# LTE_GPS.net
KiCad netlist of a schematic drawn in Altium Designer
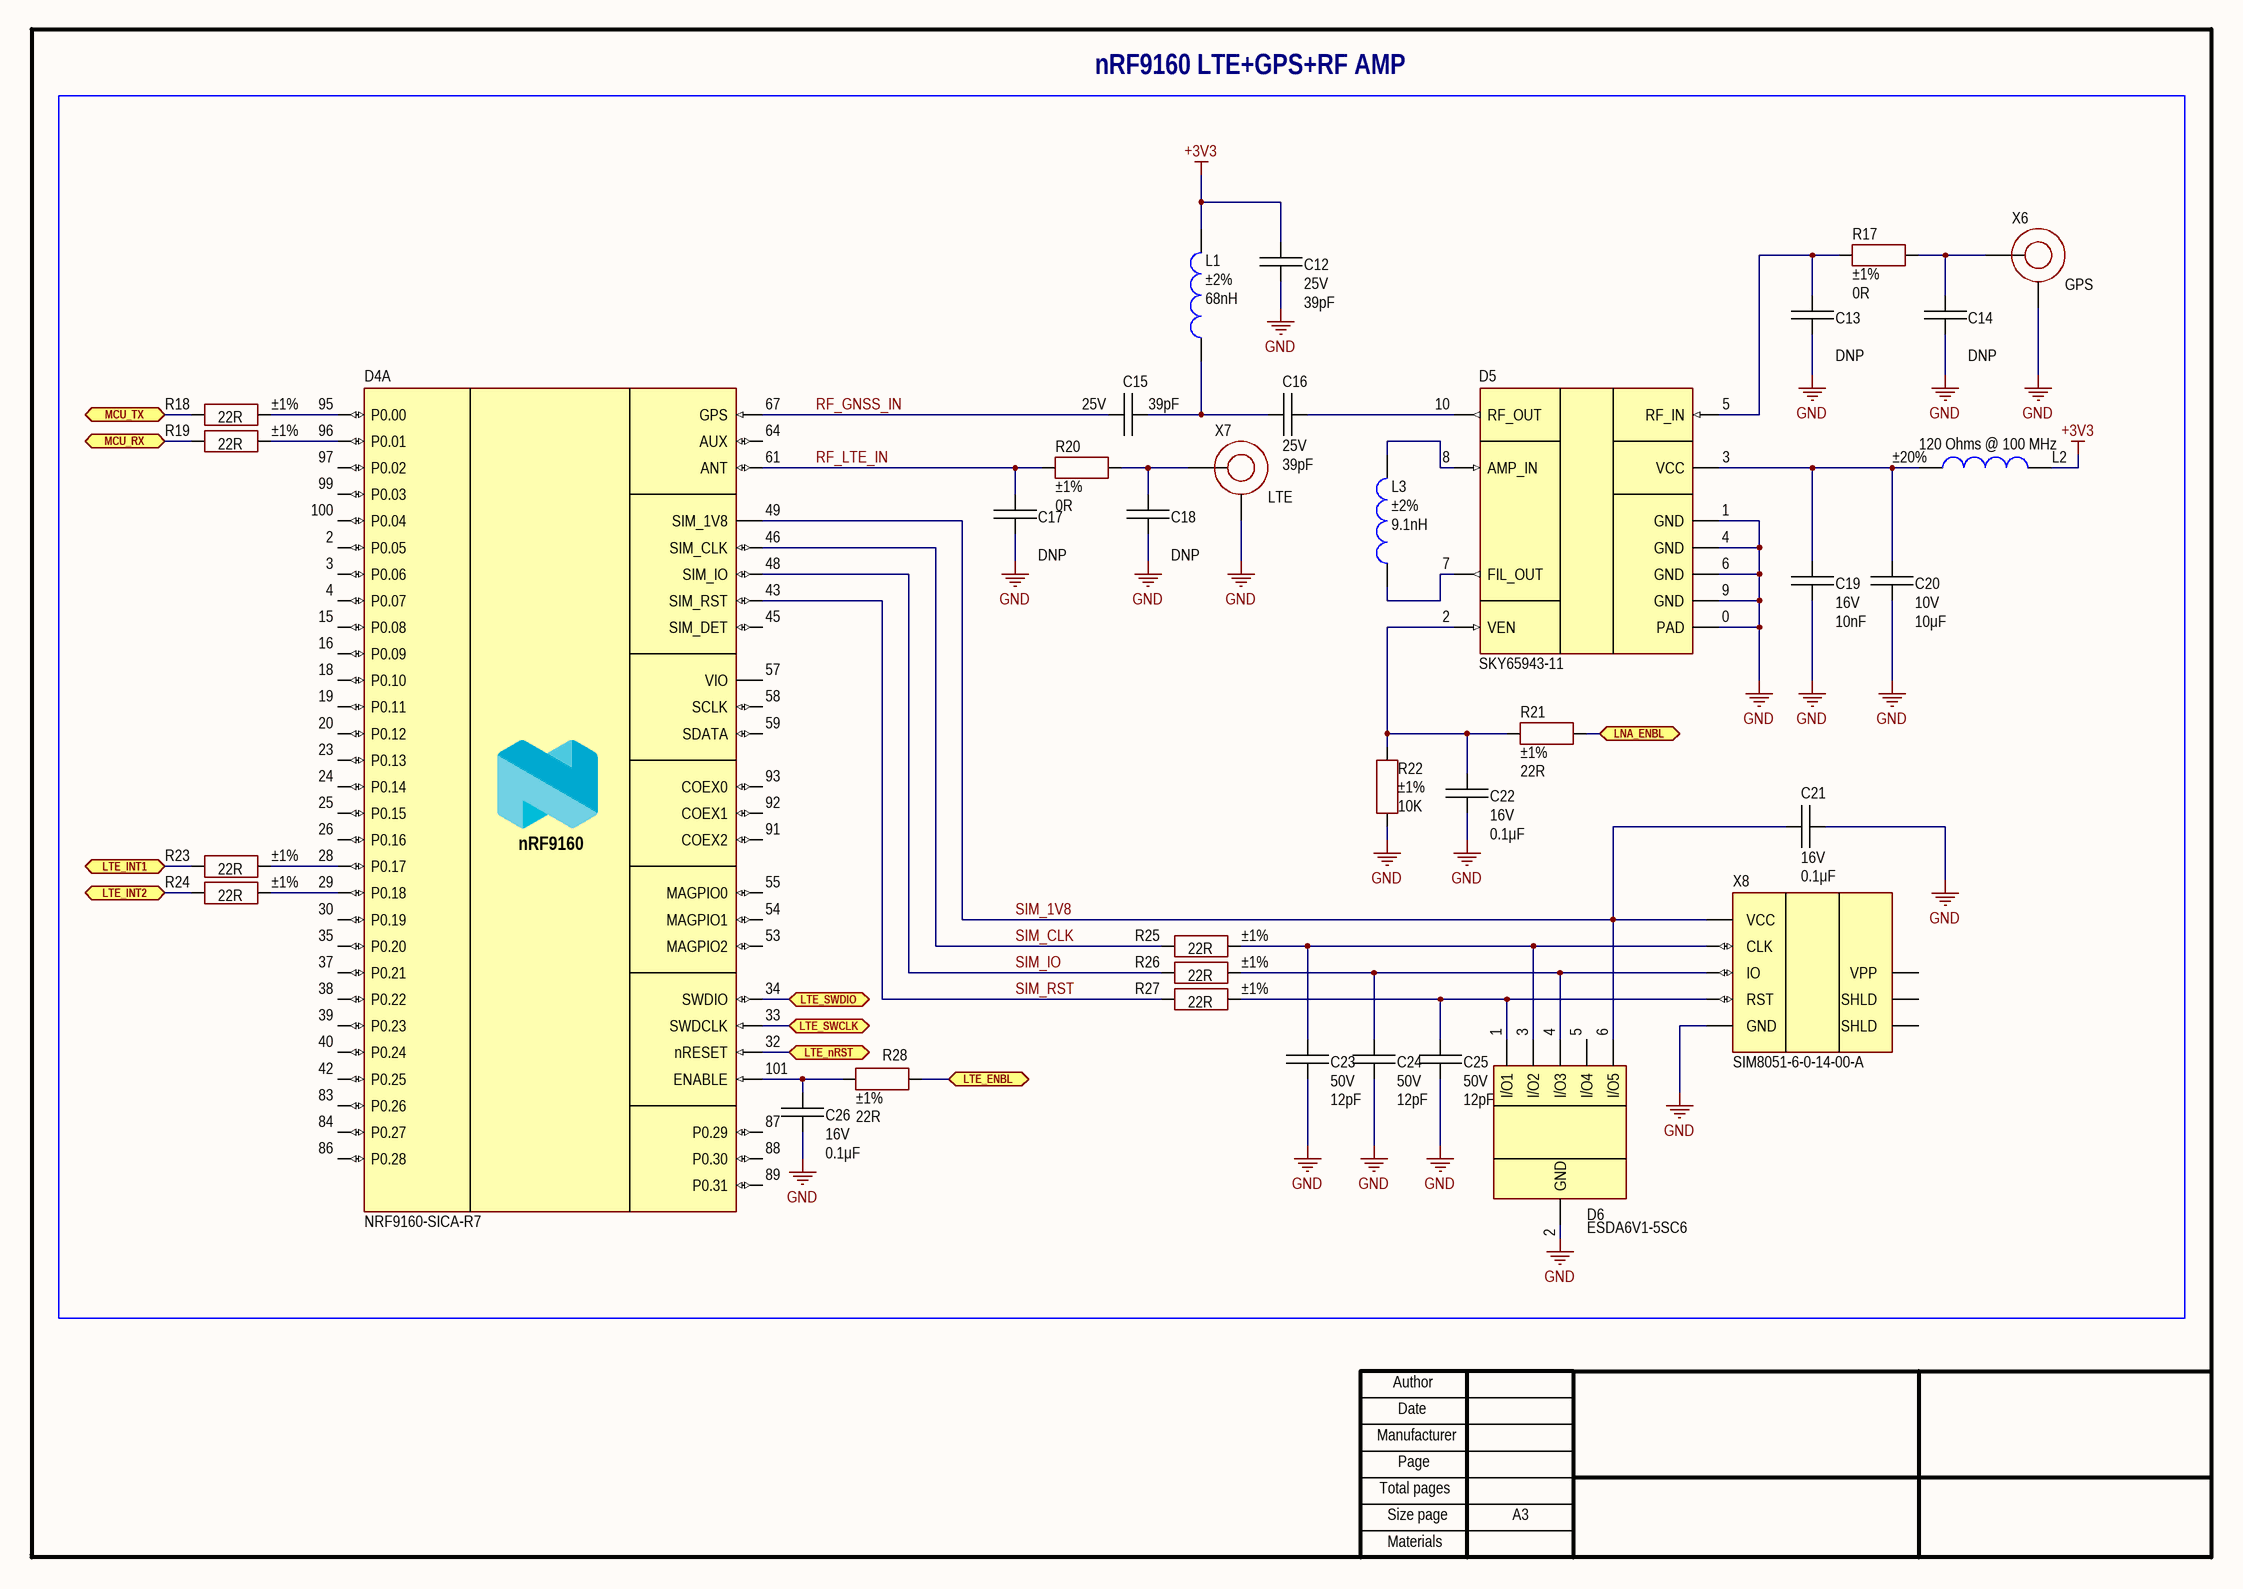
[diagram p0: LTE+GPS.SchDoc]

(export (version "E")
  (design (tool "Eeschema 10.0.6"))
  (components
    (comp (ref "C12")
      (value "39pF")
      (footprint "CAP: 0201")
      (description "39 pF ±5% 25V Ceramic Capacitor C0G, NP0 0201 (0603 Metric)")
      (fields
        (field (name "MANUFACTURER") "Murata Electronics")
        (field (name "PARTNUMBER") "GRM0335C1E390JA01D")
        (field (name "VOLTAGE") "25V")
      )
      (libsource (lib "capacitor") (part "Ceramic_0201"))
    )
    (comp (ref "C13")
      (value "DNP")
      (footprint "CAP: 0201")
      (fields (field (name "VALUEMANUFACTURERPARTNUMBER") "Ceramic capacitor, DNP, , , , 0201, -55...+125°C"))
      (libsource (lib "capacitor") (part "Ceramic_0201"))
    )
    (comp (ref "C14")
      (value "DNP")
      (footprint "CAP: 0201")
      (fields (field (name "VALUEMANUFACTURERPARTNUMBER") "Ceramic capacitor, DNP, , , , 0201, -55...+125°C"))
      (libsource (lib "capacitor") (part "Ceramic_0201"))
    )
    (comp (ref "C15")
      (value "39pF")
      (footprint "CAP: 0201")
      (description "39 pF ±5% 25V Ceramic Capacitor C0G, NP0 0201 (0603 Metric)")
      (fields
        (field (name "MANUFACTURER") "Murata Electronics")
        (field (name "PARTNUMBER") "GRM0335C1E390JA01D")
        (field (name "VOLTAGE") "25V")
      )
      (libsource (lib "capacitor") (part "Ceramic_0201"))
    )
    (comp (ref "C16")
      (value "39pF")
      (footprint "CAP: 0201")
      (description "39 pF ±5% 25V Ceramic Capacitor C0G, NP0 0201 (0603 Metric)")
      (fields
        (field (name "MANUFACTURER") "Murata Electronics")
        (field (name "PARTNUMBER") "GRM0335C1E390JA01D")
        (field (name "VOLTAGE") "25V")
      )
      (libsource (lib "capacitor") (part "Ceramic_0201"))
    )
    (comp (ref "C17")
      (value "DNP")
      (footprint "CAP: 0201")
      (fields (field (name "VALUEMANUFACTURERPARTNUMBER") "Ceramic capacitor, DNP, , , , 0201, -55...+125°C"))
      (libsource (lib "capacitor") (part "Ceramic_0201"))
    )
    (comp (ref "C18")
      (value "DNP")
      (footprint "CAP: 0201")
      (fields (field (name "VALUEMANUFACTURERPARTNUMBER") "Ceramic capacitor, DNP, , , , 0201, -55...+125°C"))
      (libsource (lib "capacitor") (part "Ceramic_0201"))
    )
    (comp (ref "C19")
      (value "10nF")
      (footprint "CAP: 0402_NO_SILK")
      (description "0.1 µF ±10% 16V Ceramic Capacitor X7R 0402 (1005 Metric)")
      (fields
        (field (name "MANUFACTURER") "Yageo")
        (field (name "PARTNUMBER") "CC0805JKNPO7BN103")
        (field (name "VOLTAGE") "16V")
      )
      (libsource (lib "capacitor") (part "Ceramic_0402"))
    )
    (comp (ref "C20")
      (value "10μF")
      (footprint "CAP: 0805")
      (description "10 µF ±10% 10V Ceramic Capacitor X7R 0805 (2012 Metric)")
      (fields
        (field (name "MANUFACTURER") "Yageo")
        (field (name "PARTNUMBER") "CC0805KFX7R6BB106")
        (field (name "VOLTAGE") "10V")
      )
      (libsource (lib "capacitor") (part "Ceramic_0805"))
    )
    (comp (ref "C21")
      (value "0.1μF")
      (footprint "CAP: 0402_NO_SILK")
      (description "0.1 µF ±10% 16V Ceramic Capacitor X7R 0402 (1005 Metric)")
      (fields
        (field (name "MANUFACTURER") "Yageo")
        (field (name "PARTNUMBER") "CC0402KRX7R7BB104")
        (field (name "VOLTAGE") "16V")
      )
      (libsource (lib "capacitor") (part "Ceramic_0402"))
    )
    (comp (ref "C22")
      (value "0.1μF")
      (footprint "CAP: 0805")
      (fields
        (field (name "MANUFACTURER") "Yageo")
        (field (name "PARTNUMBER") "CC0805KRX7R7BB104")
        (field (name "VALUEMANUFACTURERPARTNUMBER") "Ceramic capacitor, 0.1μF, X7R, ±10%, 16V, 0805, -55...+125°C")
        (field (name "VOLTAGE") "16V")
      )
      (libsource (lib "capacitor") (part "Ceramic_0805"))
    )
    (comp (ref "C23")
      (value "12pF")
      (footprint "CAP: 0805")
      (description "12 pF ±1% 50V Ceramic Capacitor C0G, NP0 0805 (2012 Metric)")
      (fields
        (field (name "MANUFACTURER") "Yageo")
        (field (name "PARTNUMBER") "CC0805FRNPO9BN120")
        (field (name "VOLTAGE") "50V")
      )
      (libsource (lib "capacitor") (part "Ceramic_0805"))
    )
    (comp (ref "C24")
      (value "12pF")
      (footprint "CAP: 0805")
      (description "12 pF ±1% 50V Ceramic Capacitor C0G, NP0 0805 (2012 Metric)")
      (fields
        (field (name "MANUFACTURER") "Yageo")
        (field (name "PARTNUMBER") "CC0805FRNPO9BN120")
        (field (name "VOLTAGE") "50V")
      )
      (libsource (lib "capacitor") (part "Ceramic_0805"))
    )
    (comp (ref "C25")
      (value "12pF")
      (footprint "CAP: 0805")
      (description "12 pF ±1% 50V Ceramic Capacitor C0G, NP0 0805 (2012 Metric)")
      (fields
        (field (name "MANUFACTURER") "Yageo")
        (field (name "PARTNUMBER") "CC0805FRNPO9BN120")
        (field (name "VOLTAGE") "50V")
      )
      (libsource (lib "capacitor") (part "Ceramic_0805"))
    )
    (comp (ref "C26")
      (value "0.1μF")
      (footprint "CAP: 0805")
      (fields
        (field (name "MANUFACTURER") "Yageo")
        (field (name "PARTNUMBER") "CC0805KRX7R7BB104")
        (field (name "VALUEMANUFACTURERPARTNUMBER") "Ceramic capacitor, 0.1μF, X7R, ±10%, 16V, 0805, -55...+125°C")
        (field (name "VOLTAGE") "16V")
      )
      (libsource (lib "capacitor") (part "Ceramic_0805"))
    )
    (comp (ref "D4")
      (value "~")
      (footprint "MOD: NRF9160")
      (description "LTE/GSM module")
      (fields
        (field (name "MANUFACTURER") "Nordic Semiconductor")
        (field (name "VALUEMANUFACTURERPARTNUMBER") "LTE/GSM module, LTE-M/NB-IoT/GPS, 2.4GHz, , , , , 3...5.5V, -40...+85°C, 127-LGA")
        (field (name "PARTNUMBER") "NRF9160-SICA-R7")
      )
      (libsource (lib "MyLib") (part "nRF9160"))
    )
    (comp (ref "D5")
      (value "~")
      (footprint "IC: SKY65943-11")
      (description "RF front-end")
      (fields
        (field (name "MANUFACTURER") "Skyworks Solutions")
        (field (name "VALUEMANUFACTURERPARTNUMBER") "IC RF amplifier, 2.7 GHz, 19dB, -40...+125°C, 10-SMD Module")
        (field (name "PARTNUMBER") "SKY65943-11")
      )
      (libsource (lib "MyLib") (part "SKY65943-11"))
    )
    (comp (ref "D6")
      (value "~")
      (footprint "SOT23-6")
      (description "TVS Array")
      (fields
        (field (name "MANUFACTURER") "STMicroelectronics")
        (field (name "VALUEMANUFACTURERPARTNUMBER") "TVS array, , 5A peak, 6.1V, , SOT-23-6, -40...+125°C")
        (field (name "PARTNUMBER") "ESDA6V1-5SC6")
      )
      (libsource (lib "MyLib") (part "ESDA6V1-5SC6"))
    )
    (comp (ref "L1")
      (value "68nH")
      (footprint "IND: 0402")
      (description "68 nH Unshielded Wirewound Inductor 320 mA 1.1Ohm Max 0402 (1005 Metric)")
      (fields
        (field (name "MANUFACTURER") "Murata Electronics")
        (field (name "PARTNUMBER") "LQW15AN68NG80D")
        (field (name "TOLERANCE") "±2%")
      )
      (libsource (lib "inductor") (part "Inductor_0402"))
    )
    (comp (ref "L2")
      (value "120 Ohms @ 100 MHz")
      (footprint "IND: 0805")
      (description "120 Ohms @ 100 MHz 1 Power Line Ferrite Bead 0805 (2012 Metric) 3A 30mOhm")
      (fields
        (field (name "MANUFACTURER") "Murata Electronics")
        (field (name "PARTNUMBER") "BLM21PG121SH1D")
        (field (name "TOLERANCE") "±20%")
      )
      (libsource (lib "inductor") (part "Inductor_0805"))
    )
    (comp (ref "L3")
      (value "9.1nH")
      (footprint "IND: 0402")
      (description "9.1 nH Unshielded Wirewound Inductor 1.4 A 80mOhm Max 0402 (1005 Metric)")
      (fields
        (field (name "MANUFACTURER") "Murata Electronics")
        (field (name "PARTNUMBER") "LQW15AN9N1G8ZD")
        (field (name "TOLERANCE") "±2%")
      )
      (libsource (lib "inductor") (part "Inductor_0402"))
    )
    (comp (ref "R17")
      (value "0R")
      (footprint "RES: 0201")
      (description "0 Ohms Jumper 0.05W, 1/20W Chip Resistor 0201 (0603 Metric) Moisture Resistant Thick Film")
      (fields
        (field (name "MANUFACTURER") "Yageo")
        (field (name "PARTNUMBER") "RC0201FR-070RL")
        (field (name "TOLERANCE") "±1%")
      )
      (libsource (lib "resistor") (part "Resistor_0201"))
    )
    (comp (ref "R18")
      (value "22R")
      (footprint "RES: 0805")
      (description "22 Ohms ±1% 0.125W, 1/8W Chip Resistor 0805 (2012 Metric) Moisture Resistant Thick Film")
      (fields
        (field (name "MANUFACTURER") "Yageo")
        (field (name "PARTNUMBER") "RC0805FR-0722RL")
        (field (name "TOLERANCE") "±1%")
      )
      (libsource (lib "resistor") (part "Resistor_0805"))
    )
    (comp (ref "R19")
      (value "22R")
      (footprint "RES: 0805")
      (description "22 Ohms ±1% 0.125W, 1/8W Chip Resistor 0805 (2012 Metric) Moisture Resistant Thick Film")
      (fields
        (field (name "MANUFACTURER") "Yageo")
        (field (name "PARTNUMBER") "RC0805FR-0722RL")
        (field (name "TOLERANCE") "±1%")
      )
      (libsource (lib "resistor") (part "Resistor_0805"))
    )
    (comp (ref "R20")
      (value "0R")
      (footprint "RES: 0201")
      (description "0 Ohms Jumper 0.05W, 1/20W Chip Resistor 0201 (0603 Metric) Moisture Resistant Thick Film")
      (fields
        (field (name "MANUFACTURER") "Yageo")
        (field (name "PARTNUMBER") "RC0201FR-070RL")
        (field (name "TOLERANCE") "±1%")
      )
      (libsource (lib "resistor") (part "Resistor_0201"))
    )
    (comp (ref "R21")
      (value "22R")
      (footprint "RES: 0805")
      (description "22 Ohms ±1% 0.125W, 1/8W Chip Resistor 0805 (2012 Metric) Moisture Resistant Thick Film")
      (fields
        (field (name "MANUFACTURER") "Yageo")
        (field (name "PARTNUMBER") "RC0805FR-0722RL")
        (field (name "TOLERANCE") "±1%")
      )
      (libsource (lib "") (part "Resistor_0805_1"))
    )
    (comp (ref "R22")
      (value "10K")
      (footprint "RES: 0805")
      (description "10 kOhms ±1% 0.125W, 1/8W Chip Resistor 0805 (2012 Metric) Moisture Resistant Thick Film")
      (fields
        (field (name "MANUFACTURER") "Yageo")
        (field (name "PARTNUMBER") "RC0805FR-0710KL")
        (field (name "TOLERANCE") "±1%")
      )
      (libsource (lib "") (part "Resistor_0805_2"))
    )
    (comp (ref "R23")
      (value "22R")
      (footprint "RES: 0805")
      (description "22 Ohms ±1% 0.125W, 1/8W Chip Resistor 0805 (2012 Metric) Moisture Resistant Thick Film")
      (fields
        (field (name "MANUFACTURER") "Yageo")
        (field (name "PARTNUMBER") "RC0805FR-0722RL")
        (field (name "TOLERANCE") "±1%")
      )
      (libsource (lib "resistor") (part "Resistor_0805"))
    )
    (comp (ref "R24")
      (value "22R")
      (footprint "RES: 0805")
      (description "22 Ohms ±1% 0.125W, 1/8W Chip Resistor 0805 (2012 Metric) Moisture Resistant Thick Film")
      (fields
        (field (name "MANUFACTURER") "Yageo")
        (field (name "PARTNUMBER") "RC0805FR-0722RL")
        (field (name "TOLERANCE") "±1%")
      )
      (libsource (lib "resistor") (part "Resistor_0805"))
    )
    (comp (ref "R25")
      (value "22R")
      (footprint "RES: 0805")
      (description "22 Ohms ±1% 0.125W, 1/8W Chip Resistor 0805 (2012 Metric) Moisture Resistant Thick Film")
      (fields
        (field (name "MANUFACTURER") "Yageo")
        (field (name "PARTNUMBER") "RC0805FR-0722RL")
        (field (name "TOLERANCE") "±1%")
      )
      (libsource (lib "resistor") (part "Resistor_0805"))
    )
    (comp (ref "R26")
      (value "22R")
      (footprint "RES: 0805")
      (description "22 Ohms ±1% 0.125W, 1/8W Chip Resistor 0805 (2012 Metric) Moisture Resistant Thick Film")
      (fields
        (field (name "MANUFACTURER") "Yageo")
        (field (name "PARTNUMBER") "RC0805FR-0722RL")
        (field (name "TOLERANCE") "±1%")
      )
      (libsource (lib "resistor") (part "Resistor_0805"))
    )
    (comp (ref "R27")
      (value "22R")
      (footprint "RES: 0805")
      (description "22 Ohms ±1% 0.125W, 1/8W Chip Resistor 0805 (2012 Metric) Moisture Resistant Thick Film")
      (fields
        (field (name "MANUFACTURER") "Yageo")
        (field (name "PARTNUMBER") "RC0805FR-0722RL")
        (field (name "TOLERANCE") "±1%")
      )
      (libsource (lib "resistor") (part "Resistor_0805"))
    )
    (comp (ref "R28")
      (value "22R")
      (footprint "RES: 0805")
      (description "22 Ohms ±1% 0.125W, 1/8W Chip Resistor 0805 (2012 Metric) Moisture Resistant Thick Film")
      (fields
        (field (name "MANUFACTURER") "Yageo")
        (field (name "PARTNUMBER") "RC0805FR-0722RL")
        (field (name "TOLERANCE") "±1%")
      )
      (libsource (lib "") (part "Resistor_0805_1"))
    )
    (comp (ref "X6")
      (value "~")
      (footprint "CON: u.Fl")
      (description "U.FL (UMCC) Connector Receptacle, Male Pin 50Ohm Surface Mount Solder")
      (fields
        (field (name "MANUFACTURER") "Hirose Electric")
        (field (name "VALUEMANUFACTURERPARTNUMBER") "Connector u.FL, 50 Ohm, 6GHz")
        (field (name "COMMENTTEXT") "GPS")
      )
      (libsource (lib "connector") (part "Connector_uFL"))
    )
    (comp (ref "X7")
      (value "~")
      (footprint "CON: u.Fl")
      (description "U.FL (UMCC) Connector Receptacle, Male Pin 50Ohm Surface Mount Solder")
      (fields
        (field (name "MANUFACTURER") "Hirose Electric")
        (field (name "VALUEMANUFACTURERPARTNUMBER") "Connector u.FL, 50 Ohm, 6GHz")
        (field (name "COMMENTTEXT") "LTE")
      )
      (libsource (lib "connector") (part "Connector_uFL"))
    )
    (comp (ref "X8")
      (value "~")
      (footprint "CON: SIM8051-6-0-14-00")
      (description "Connector")
      (fields
        (field (name "MANUFACTURER") "GCT")
        (field (name "VALUEMANUFACTURERPARTNUMBER") "Nano SIM, , , , ")
        (field (name "COMMENTTEXT") "SIM8051-6-0-14-00-A")
      )
      (libsource (lib "MyLib") (part "SIM8051-6-0-14-00-A"))
    )
  )
  (nets
    (net (code "1") (name "+3V3") (class "Default")
      (node (ref "C12") (pin "1") (pinfunction "1_1") (pintype "passive"))
      (node (ref "L1") (pin "1") (pinfunction "1_1") (pintype "passive"))
      (node (ref "L2") (pin "1") (pinfunction "1_1") (pintype "passive"))
    )
    (net (code "2") (name "/LNA_ENBL") (class "Default")
      (node (ref "R21") (pin "1") (pinfunction "1_1") (pintype "passive"))
    )
    (net (code "3") (name "/LTE_ENBL") (class "Default")
      (node (ref "R28") (pin "1") (pinfunction "1_1") (pintype "passive"))
    )
    (net (code "4") (name "/LTE_INT1") (class "Default")
      (node (ref "R23") (pin "1") (pinfunction "1_1") (pintype "passive"))
    )
    (net (code "5") (name "/LTE_INT2") (class "Default")
      (node (ref "R24") (pin "1") (pinfunction "1_1") (pintype "passive"))
    )
    (net (code "6") (name "/LTE_SWCLK") (class "Default")
      (node (ref "D4") (pin "33") (pinfunction "SWDCLK_33") (pintype "input"))
    )
    (net (code "7") (name "/LTE_SWDIO") (class "Default")
      (node (ref "D4") (pin "34") (pinfunction "SWDIO_34") (pintype "bidirectional"))
    )
    (net (code "8") (name "/LTE_nRST") (class "Default")
      (node (ref "D4") (pin "32") (pinfunction "nRESET_32") (pintype "input"))
    )
    (net (code "9") (name "/MCU_RX") (class "Default")
      (node (ref "R19") (pin "1") (pinfunction "1_1") (pintype "passive"))
    )
    (net (code "10") (name "/MCU_TX") (class "Default")
      (node (ref "R18") (pin "1") (pinfunction "1_1") (pintype "passive"))
    )
    (net (code "11") (name "/RF_GNSS_IN") (class "Default")
      (node (ref "C15") (pin "2") (pinfunction "2_2") (pintype "passive"))
      (node (ref "D4") (pin "67") (pinfunction "GPS_67") (pintype "input"))
    )
    (net (code "12") (name "/RF_LTE_IN") (class "Default")
      (node (ref "C17") (pin "2") (pinfunction "2_2") (pintype "passive"))
      (node (ref "D4") (pin "61") (pinfunction "ANT_61") (pintype "bidirectional"))
      (node (ref "R20") (pin "2") (pinfunction "2_2") (pintype "passive"))
    )
    (net (code "13") (name "/SIM_1V8") (class "Default")
      (node (ref "C21") (pin "1") (pinfunction "1_1") (pintype "passive"))
      (node (ref "D4") (pin "49") (pinfunction "SIM_1V8_49") (pintype "power_in"))
      (node (ref "D6") (pin "6") (pinfunction "I/O5_6") (pintype "passive"))
      (node (ref "X8") (pin "C1") (pinfunction "VCC_C1") (pintype "power_in"))
    )
    (net (code "14") (name "/SIM_CLK") (class "Default")
      (node (ref "D4") (pin "46") (pinfunction "SIM_CLK_46") (pintype "bidirectional"))
      (node (ref "R25") (pin "1") (pinfunction "1_1") (pintype "passive"))
    )
    (net (code "15") (name "/SIM_IO") (class "Default")
      (node (ref "D4") (pin "48") (pinfunction "SIM_IO_48") (pintype "bidirectional"))
      (node (ref "R26") (pin "1") (pinfunction "1_1") (pintype "passive"))
    )
    (net (code "16") (name "/SIM_RST") (class "Default")
      (node (ref "D4") (pin "43") (pinfunction "SIM_RST_43") (pintype "bidirectional"))
      (node (ref "R27") (pin "1") (pinfunction "1_1") (pintype "passive"))
    )
    (net (code "17") (name "GND") (class "Default")
      (node (ref "C12") (pin "2") (pinfunction "2_2") (pintype "passive"))
      (node (ref "C13") (pin "1") (pinfunction "1_1") (pintype "passive"))
      (node (ref "C14") (pin "1") (pinfunction "1_1") (pintype "passive"))
      (node (ref "C17") (pin "1") (pinfunction "1_1") (pintype "passive"))
      (node (ref "C18") (pin "1") (pinfunction "1_1") (pintype "passive"))
      (node (ref "C19") (pin "1") (pinfunction "1_1") (pintype "passive"))
      (node (ref "C20") (pin "1") (pinfunction "1_1") (pintype "passive"))
      (node (ref "C21") (pin "2") (pinfunction "2_2") (pintype "passive"))
      (node (ref "C22") (pin "1") (pinfunction "1_1") (pintype "passive"))
      (node (ref "C23") (pin "1") (pinfunction "1_1") (pintype "passive"))
      (node (ref "C24") (pin "1") (pinfunction "1_1") (pintype "passive"))
      (node (ref "C25") (pin "1") (pinfunction "1_1") (pintype "passive"))
      (node (ref "C26") (pin "1") (pinfunction "1_1") (pintype "passive"))
      (node (ref "D5") (pin "0") (pinfunction "PAD_0") (pintype "power_in"))
      (node (ref "D5") (pin "1") (pinfunction "GND_1") (pintype "power_in"))
      (node (ref "D5") (pin "4") (pinfunction "GND_4") (pintype "power_in"))
      (node (ref "D5") (pin "6") (pinfunction "GND_6") (pintype "power_in"))
      (node (ref "D5") (pin "9") (pinfunction "GND_9") (pintype "power_in"))
      (node (ref "D6") (pin "2") (pinfunction "GND_2") (pintype "passive"))
      (node (ref "R22") (pin "1") (pinfunction "1_1") (pintype "passive"))
      (node (ref "X6") (pin "2") (pinfunction "2_2") (pintype "passive"))
      (node (ref "X7") (pin "2") (pinfunction "2_2") (pintype "passive"))
      (node (ref "X8") (pin "C5") (pinfunction "GND_C5") (pintype "power_in"))
    )
    (net (code "18") (name "Net-(C14-Pad2)") (class "Default")
      (node (ref "C14") (pin "2") (pinfunction "2_2") (pintype "passive"))
      (node (ref "R17") (pin "1") (pinfunction "1_1") (pintype "passive"))
      (node (ref "X6") (pin "1") (pinfunction "1_1") (pintype "passive"))
    )
    (net (code "19") (name "Net-(C15-Pad1)") (class "Default")
      (node (ref "C15") (pin "1") (pinfunction "1_1") (pintype "passive"))
      (node (ref "C16") (pin "2") (pinfunction "2_2") (pintype "passive"))
      (node (ref "L1") (pin "2") (pinfunction "2_2") (pintype "passive"))
    )
    (net (code "20") (name "Net-(C18-Pad2)") (class "Default")
      (node (ref "C18") (pin "2") (pinfunction "2_2") (pintype "passive"))
      (node (ref "R20") (pin "1") (pinfunction "1_1") (pintype "passive"))
      (node (ref "X7") (pin "1") (pinfunction "1_1") (pintype "passive"))
    )
    (net (code "21") (name "Net-(D4A-ENABLE)") (class "Default")
      (node (ref "C26") (pin "2") (pinfunction "2_2") (pintype "passive"))
      (node (ref "D4") (pin "101") (pinfunction "ENABLE_101") (pintype "input"))
      (node (ref "R28") (pin "2") (pinfunction "2_2") (pintype "passive"))
    )
    (net (code "22") (name "Net-(D4A-P0.00)") (class "Default")
      (node (ref "D4") (pin "95") (pinfunction "P0.00_95") (pintype "bidirectional"))
      (node (ref "R18") (pin "2") (pinfunction "2_2") (pintype "passive"))
    )
    (net (code "23") (name "Net-(D4A-P0.01)") (class "Default")
      (node (ref "D4") (pin "96") (pinfunction "P0.01_96") (pintype "bidirectional"))
      (node (ref "R19") (pin "2") (pinfunction "2_2") (pintype "passive"))
    )
    (net (code "24") (name "Net-(D4A-P0.17)") (class "Default")
      (node (ref "D4") (pin "28") (pinfunction "P0.17_28") (pintype "bidirectional"))
      (node (ref "R23") (pin "2") (pinfunction "2_2") (pintype "passive"))
    )
    (net (code "25") (name "Net-(D4A-P0.18)") (class "Default")
      (node (ref "D4") (pin "29") (pinfunction "P0.18_29") (pintype "bidirectional"))
      (node (ref "R24") (pin "2") (pinfunction "2_2") (pintype "passive"))
    )
    (net (code "26") (name "Net-(D5-AMP_IN)") (class "Default")
      (node (ref "D5") (pin "8") (pinfunction "AMP_IN_8") (pintype "input"))
      (node (ref "L3") (pin "1") (pinfunction "1_1") (pintype "passive"))
    )
    (net (code "27") (name "Net-(D5-FIL_OUT)") (class "Default")
      (node (ref "D5") (pin "7") (pinfunction "FIL_OUT_7") (pintype "output"))
      (node (ref "L3") (pin "2") (pinfunction "2_2") (pintype "passive"))
    )
    (net (code "28") (name "Net-(D5-RF_IN)") (class "Default")
      (node (ref "C13") (pin "2") (pinfunction "2_2") (pintype "passive"))
      (node (ref "D5") (pin "5") (pinfunction "RF_IN_5") (pintype "input"))
      (node (ref "R17") (pin "2") (pinfunction "2_2") (pintype "passive"))
    )
    (net (code "29") (name "Net-(D5-RF_OUT)") (class "Default")
      (node (ref "C16") (pin "1") (pinfunction "1_1") (pintype "passive"))
      (node (ref "D5") (pin "10") (pinfunction "RF_OUT_10") (pintype "output"))
    )
    (net (code "30") (name "Net-(D5-VCC)") (class "Default")
      (node (ref "C19") (pin "2") (pinfunction "2_2") (pintype "passive"))
      (node (ref "C20") (pin "2") (pinfunction "2_2") (pintype "passive"))
      (node (ref "D5") (pin "3") (pinfunction "VCC_3") (pintype "power_in"))
      (node (ref "L2") (pin "2") (pinfunction "2_2") (pintype "passive"))
    )
    (net (code "31") (name "Net-(D5-VEN)") (class "Default")
      (node (ref "C22") (pin "2") (pinfunction "2_2") (pintype "passive"))
      (node (ref "D5") (pin "2") (pinfunction "VEN_2") (pintype "input"))
      (node (ref "R21") (pin "2") (pinfunction "2_2") (pintype "passive"))
      (node (ref "R22") (pin "2") (pinfunction "2_2") (pintype "passive"))
    )
    (net (code "32") (name "Net-(D6-I{slash}O1)") (class "Default")
      (node (ref "C25") (pin "2") (pinfunction "2_2") (pintype "passive"))
      (node (ref "D6") (pin "1") (pinfunction "I/O1_1") (pintype "passive"))
      (node (ref "R27") (pin "2") (pinfunction "2_2") (pintype "passive"))
      (node (ref "X8") (pin "C2") (pinfunction "RST_C2") (pintype "bidirectional"))
    )
    (net (code "33") (name "Net-(D6-I{slash}O2)") (class "Default")
      (node (ref "C23") (pin "2") (pinfunction "2_2") (pintype "passive"))
      (node (ref "D6") (pin "3") (pinfunction "I/O2_3") (pintype "passive"))
      (node (ref "R25") (pin "2") (pinfunction "2_2") (pintype "passive"))
      (node (ref "X8") (pin "C3") (pinfunction "CLK_C3") (pintype "bidirectional"))
    )
    (net (code "34") (name "Net-(D6-I{slash}O3)") (class "Default")
      (node (ref "C24") (pin "2") (pinfunction "2_2") (pintype "passive"))
      (node (ref "D6") (pin "4") (pinfunction "I/O3_4") (pintype "passive"))
      (node (ref "R26") (pin "2") (pinfunction "2_2") (pintype "passive"))
      (node (ref "X8") (pin "C7") (pinfunction "IO_C7") (pintype "bidirectional"))
    )
    (net (code "35") (name "unconnected-(D4A-AUX-Pad64)") (class "Default")
      (node (ref "D4") (pin "64") (pinfunction "AUX_64") (pintype "bidirectional"))
    )
    (net (code "36") (name "unconnected-(D4A-COEX0-Pad93)") (class "Default")
      (node (ref "D4") (pin "93") (pinfunction "COEX0_93") (pintype "bidirectional"))
    )
    (net (code "37") (name "unconnected-(D4A-COEX1-Pad92)") (class "Default")
      (node (ref "D4") (pin "92") (pinfunction "COEX1_92") (pintype "bidirectional"))
    )
    (net (code "38") (name "unconnected-(D4A-COEX2-Pad91)") (class "Default")
      (node (ref "D4") (pin "91") (pinfunction "COEX2_91") (pintype "bidirectional"))
    )
    (net (code "39") (name "unconnected-(D4A-MAGPIO0-Pad55)") (class "Default")
      (node (ref "D4") (pin "55") (pinfunction "MAGPIO0_55") (pintype "bidirectional"))
    )
    (net (code "40") (name "unconnected-(D4A-MAGPIO1-Pad54)") (class "Default")
      (node (ref "D4") (pin "54") (pinfunction "MAGPIO1_54") (pintype "bidirectional"))
    )
    (net (code "41") (name "unconnected-(D4A-MAGPIO2-Pad53)") (class "Default")
      (node (ref "D4") (pin "53") (pinfunction "MAGPIO2_53") (pintype "bidirectional"))
    )
    (net (code "42") (name "unconnected-(D4A-P0.02-Pad97)") (class "Default")
      (node (ref "D4") (pin "97") (pinfunction "P0.02_97") (pintype "bidirectional"))
    )
    (net (code "43") (name "unconnected-(D4A-P0.03-Pad99)") (class "Default")
      (node (ref "D4") (pin "99") (pinfunction "P0.03_99") (pintype "bidirectional"))
    )
    (net (code "44") (name "unconnected-(D4A-P0.04-Pad100)") (class "Default")
      (node (ref "D4") (pin "100") (pinfunction "P0.04_100") (pintype "bidirectional"))
    )
    (net (code "45") (name "unconnected-(D4A-P0.05-Pad2)") (class "Default")
      (node (ref "D4") (pin "2") (pinfunction "P0.05_2") (pintype "bidirectional"))
    )
    (net (code "46") (name "unconnected-(D4A-P0.06-Pad3)") (class "Default")
      (node (ref "D4") (pin "3") (pinfunction "P0.06_3") (pintype "bidirectional"))
    )
    (net (code "47") (name "unconnected-(D4A-P0.07-Pad4)") (class "Default")
      (node (ref "D4") (pin "4") (pinfunction "P0.07_4") (pintype "bidirectional"))
    )
    (net (code "48") (name "unconnected-(D4A-P0.08-Pad15)") (class "Default")
      (node (ref "D4") (pin "15") (pinfunction "P0.08_15") (pintype "bidirectional"))
    )
    (net (code "49") (name "unconnected-(D4A-P0.09-Pad16)") (class "Default")
      (node (ref "D4") (pin "16") (pinfunction "P0.09_16") (pintype "bidirectional"))
    )
    (net (code "50") (name "unconnected-(D4A-P0.10-Pad18)") (class "Default")
      (node (ref "D4") (pin "18") (pinfunction "P0.10_18") (pintype "bidirectional"))
    )
    (net (code "51") (name "unconnected-(D4A-P0.11-Pad19)") (class "Default")
      (node (ref "D4") (pin "19") (pinfunction "P0.11_19") (pintype "bidirectional"))
    )
    (net (code "52") (name "unconnected-(D4A-P0.12-Pad20)") (class "Default")
      (node (ref "D4") (pin "20") (pinfunction "P0.12_20") (pintype "bidirectional"))
    )
    (net (code "53") (name "unconnected-(D4A-P0.13-Pad23)") (class "Default")
      (node (ref "D4") (pin "23") (pinfunction "P0.13_23") (pintype "bidirectional"))
    )
    (net (code "54") (name "unconnected-(D4A-P0.14-Pad24)") (class "Default")
      (node (ref "D4") (pin "24") (pinfunction "P0.14_24") (pintype "bidirectional"))
    )
    (net (code "55") (name "unconnected-(D4A-P0.15-Pad25)") (class "Default")
      (node (ref "D4") (pin "25") (pinfunction "P0.15_25") (pintype "bidirectional"))
    )
    (net (code "56") (name "unconnected-(D4A-P0.16-Pad26)") (class "Default")
      (node (ref "D4") (pin "26") (pinfunction "P0.16_26") (pintype "bidirectional"))
    )
    (net (code "57") (name "unconnected-(D4A-P0.19-Pad30)") (class "Default")
      (node (ref "D4") (pin "30") (pinfunction "P0.19_30") (pintype "bidirectional"))
    )
    (net (code "58") (name "unconnected-(D4A-P0.20-Pad35)") (class "Default")
      (node (ref "D4") (pin "35") (pinfunction "P0.20_35") (pintype "bidirectional"))
    )
    (net (code "59") (name "unconnected-(D4A-P0.21-Pad37)") (class "Default")
      (node (ref "D4") (pin "37") (pinfunction "P0.21_37") (pintype "bidirectional"))
    )
    (net (code "60") (name "unconnected-(D4A-P0.22-Pad38)") (class "Default")
      (node (ref "D4") (pin "38") (pinfunction "P0.22_38") (pintype "bidirectional"))
    )
    (net (code "61") (name "unconnected-(D4A-P0.23-Pad39)") (class "Default")
      (node (ref "D4") (pin "39") (pinfunction "P0.23_39") (pintype "bidirectional"))
    )
    (net (code "62") (name "unconnected-(D4A-P0.24-Pad40)") (class "Default")
      (node (ref "D4") (pin "40") (pinfunction "P0.24_40") (pintype "bidirectional"))
    )
    (net (code "63") (name "unconnected-(D4A-P0.25-Pad42)") (class "Default")
      (node (ref "D4") (pin "42") (pinfunction "P0.25_42") (pintype "bidirectional"))
    )
    (net (code "64") (name "unconnected-(D4A-P0.26-Pad83)") (class "Default")
      (node (ref "D4") (pin "83") (pinfunction "P0.26_83") (pintype "bidirectional"))
    )
    (net (code "65") (name "unconnected-(D4A-P0.27-Pad84)") (class "Default")
      (node (ref "D4") (pin "84") (pinfunction "P0.27_84") (pintype "bidirectional"))
    )
    (net (code "66") (name "unconnected-(D4A-P0.28-Pad86)") (class "Default")
      (node (ref "D4") (pin "86") (pinfunction "P0.28_86") (pintype "bidirectional"))
    )
    (net (code "67") (name "unconnected-(D4A-P0.29-Pad87)") (class "Default")
      (node (ref "D4") (pin "87") (pinfunction "P0.29_87") (pintype "bidirectional"))
    )
    (net (code "68") (name "unconnected-(D4A-P0.30-Pad88)") (class "Default")
      (node (ref "D4") (pin "88") (pinfunction "P0.30_88") (pintype "bidirectional"))
    )
    (net (code "69") (name "unconnected-(D4A-P0.31-Pad89)") (class "Default")
      (node (ref "D4") (pin "89") (pinfunction "P0.31_89") (pintype "bidirectional"))
    )
    (net (code "70") (name "unconnected-(D4A-SCLK-Pad58)") (class "Default")
      (node (ref "D4") (pin "58") (pinfunction "SCLK_58") (pintype "bidirectional"))
    )
    (net (code "71") (name "unconnected-(D4A-SDATA-Pad59)") (class "Default")
      (node (ref "D4") (pin "59") (pinfunction "SDATA_59") (pintype "bidirectional"))
    )
    (net (code "72") (name "unconnected-(D4A-SIM_DET-Pad45)") (class "Default")
      (node (ref "D4") (pin "45") (pinfunction "SIM_DET_45") (pintype "bidirectional"))
    )
    (net (code "73") (name "unconnected-(D4A-VIO-Pad57)") (class "Default")
      (node (ref "D4") (pin "57") (pinfunction "VIO_57") (pintype "power_in"))
    )
    (net (code "74") (name "unconnected-(D6-I{slash}O4-Pad5)") (class "Default")
      (node (ref "D6") (pin "5") (pinfunction "I/O4_5") (pintype "passive"))
    )
    (net (code "75") (name "unconnected-(X8-SHLD-PadC4)") (class "Default")
      (node (ref "X8") (pin "C4") (pinfunction "SHLD_C4") (pintype "passive"))
    )
    (net (code "76") (name "unconnected-(X8-SHLD-PadC8)") (class "Default")
      (node (ref "X8") (pin "C8") (pinfunction "SHLD_C8") (pintype "passive"))
    )
    (net (code "77") (name "unconnected-(X8-VPP-PadC6)") (class "Default")
      (node (ref "X8") (pin "C6") (pinfunction "VPP_C6") (pintype "power_in"))
    )
  )
)
